# RENEWAA.net
KiCad netlist of a schematic drawn in Altium Designer
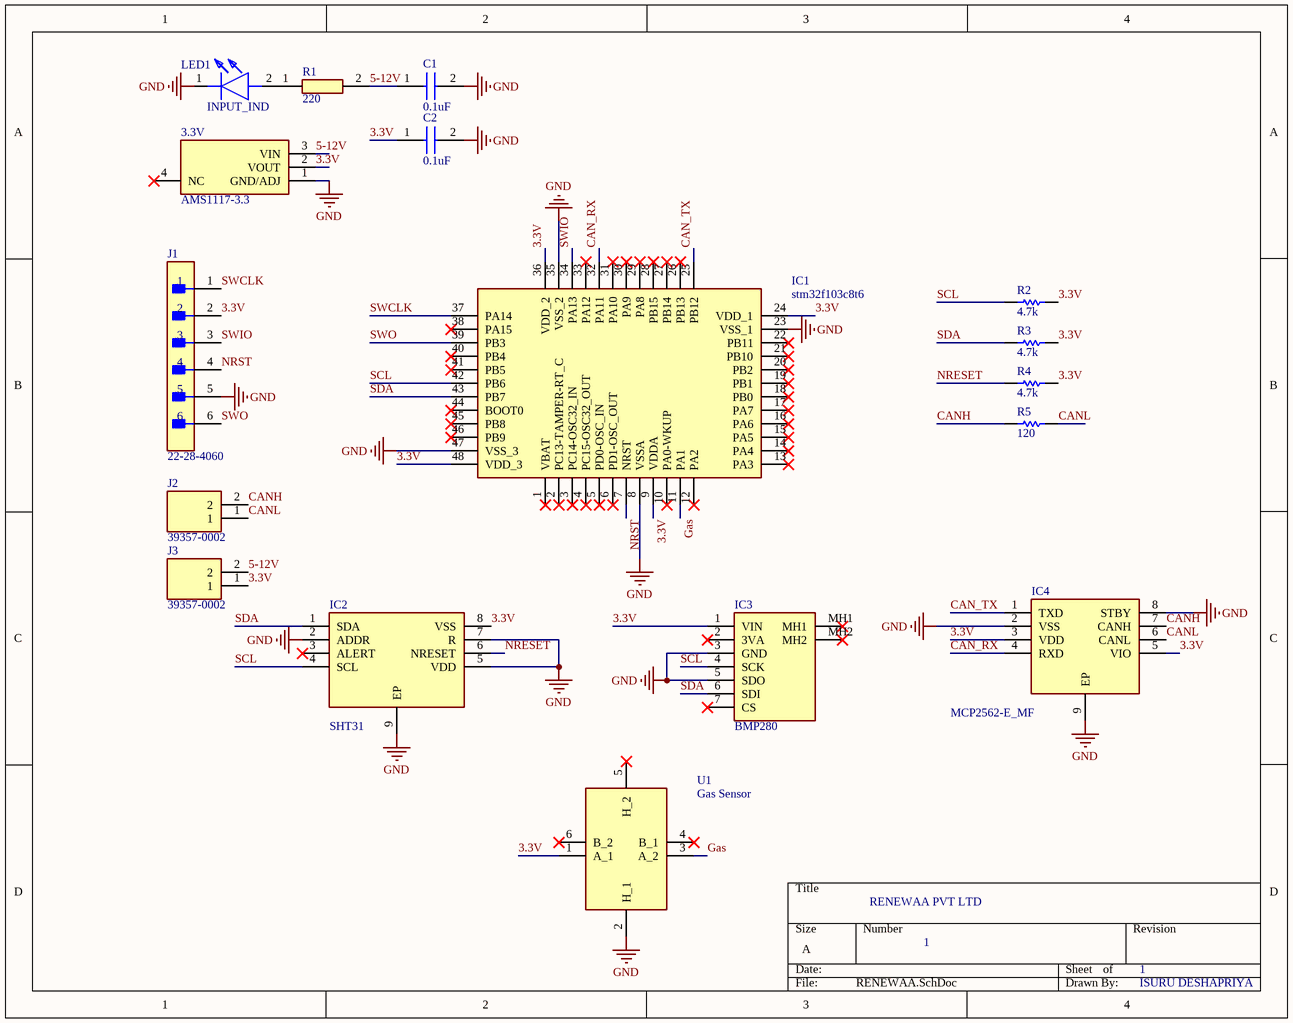
[diagram p0: RENEWAA.SchDoc]

(export (version "E")
  (design (tool "Eeschema 10.0.6"))
  (components
    (comp (ref "3.3V")
      (value "AMS1117-3.3")
      (footprint "SamacSys:SOT229P700X180-4N")
      (description "Integrated Circuit")
      (libsource (lib "*") (part "AMS1117-3.3"))
    )
    (comp (ref "C1")
      (value "0.1uF")
      (footprint "SamacSys:CAPC1005X56N")
      (description "Capacitor")
      (fields
        (field (name "MANUFACTURER_PART_NUMBER") "04024D106MAT2A")
        (field (name "MOUSER PART NUMBER") "581-04024D106MAT2A")
      )
      (libsource (lib "*") (part "04024D106MAT2A"))
    )
    (comp (ref "C2")
      (value "0.1uF")
      (footprint "SamacSys:CAPC1005X56N")
      (description "Capacitor")
      (fields
        (field (name "MANUFACTURER_PART_NUMBER") "04024D106MAT2A")
        (field (name "MOUSER PART NUMBER") "581-04024D106MAT2A")
      )
      (libsource (lib "*") (part "04024D106MAT2A"))
    )
    (comp (ref "IC1")
      (value "stm32f103c8t6")
      (footprint "SamacSys:QFP50P900X900X160-48N")
      (description "Integrated Circuit")
      (fields
        (field (name "MOUSER PART NUMBER") "511-STM32F103C8T6")
        (field (name "ARROW PART NUMBER") "STM32F103C8T6")
      )
      (libsource (lib "*") (part "stm32f103c8t6"))
    )
    (comp (ref "IC2")
      (value "SHT31")
      (footprint "SamacSys:SON50P250X250X100-9N-D")
      (description "Integrated Circuit")
      (fields
        (field (name "MANUFACTURER_PART_NUMBER") "SHT31-DIS-B10KS")
        (field (name "MOUSER PART NUMBER") "403-SHT31-DIS-B10KS")
      )
      (libsource (lib "*") (part "SHT31-DIS-B10KS"))
    )
    (comp (ref "IC3")
      (value "BMP280")
      (footprint "SamacSys:2651")
      (description "Integrated Circuit")
      (fields (field (name "MANUFACTURER_PART_NUMBER") "2651") (field (name "MOUSER PART NUMBER") "485-2651"))
      (libsource (lib "*") (part "2651"))
    )
    (comp (ref "IC4")
      (value "MCP2562-E_MF")
      (footprint "SamacSys:SON65P300X300X100-9N-D")
      (description "Integrated Circuit")
      (fields
        (field (name "MANUFACTURER_PART_NUMBER") "MCP2562-E/MF")
        (field (name "MOUSER PART NUMBER") "579-MCP2562-E/MF")
      )
      (libsource (lib "*") (part "MCP2562-E_MF"))
    )
    (comp (ref "J1")
      (value "22-28-4060")
      (footprint "FP-22-28-4060-MFG")
      (description "CONN HEADER VERT 6POS 2.54MM")
      (libsource (lib "Altium Content Vault") (part "f2cb566baf1c37ab5a3b8e90bbeafd6"))
    )
    (comp (ref "J2")
      (value "39357-0002")
      (footprint "SamacSys:393570002")
      (description "Connector")
      (fields (field (name "MOUSER PART NUMBER") "538-39357-0002"))
      (libsource (lib "*") (part "39357-0002"))
    )
    (comp (ref "J3")
      (value "39357-0002")
      (footprint "SamacSys:393570002")
      (description "Connector")
      (fields (field (name "MOUSER PART NUMBER") "538-39357-0002"))
      (libsource (lib "*") (part "39357-0002"))
    )
    (comp (ref "LED1")
      (value "INPUT_IND")
      (footprint "SamacSys:1221S2CFR2S2L2C")
      (description "LED")
      (fields (field (name "MANUFACTURER_PART_NUMBER") "12-21/S2C-FR2S2L/2C"))
      (libsource (lib "*") (part "12-21_S2C-FR2S2L_2C"))
    )
    (comp (ref "R1")
      (value "220")
      (footprint "SamacSys:RESC1005X40N")
      (description "Resistor")
      (fields
        (field (name "MANUFACTURER_PART_NUMBER") "CR0402-FX-2200GLF")
        (field (name "MOUSER PART NUMBER") "652-CR0402FX-2200GLF")
      )
      (libsource (lib "*") (part "CR0402-FX-2200GLF"))
    )
    (comp (ref "R2")
      (value "4.7k")
      (footprint "RESC3216X60X45ML15T20")
      (description "Chip Resistor, 4.7 KOhm, +/- 1%, 0.25 W, -55 to 155 degC, 1206 (3216 Metric), RoHS, Tape and Reel")
      (fields (field (name "MANUFACTURER") "Vishay Semiconductor") (field (name "TOLERANCE") "1%"))
      (libsource (lib "Altium Content Vault") (part "RES-2"))
    )
    (comp (ref "R3")
      (value "4.7k")
      (footprint "RESC3216X60X45ML15T20")
      (description "Chip Resistor, 4.7 KOhm, +/- 1%, 0.25 W, -55 to 155 degC, 1206 (3216 Metric), RoHS, Tape and Reel")
      (fields (field (name "MANUFACTURER") "Vishay Semiconductor") (field (name "TOLERANCE") "1%"))
      (libsource (lib "Altium Content Vault") (part "RES-2"))
    )
    (comp (ref "R4")
      (value "4.7k")
      (footprint "RESC3216X60X45ML15T20")
      (description "Chip Resistor, 4.7 KOhm, +/- 1%, 0.25 W, -55 to 155 degC, 1206 (3216 Metric), RoHS, Tape and Reel")
      (fields (field (name "MANUFACTURER") "Vishay Semiconductor") (field (name "TOLERANCE") "1%"))
      (libsource (lib "Altium Content Vault") (part "RES-2"))
    )
    (comp (ref "R5")
      (value "120")
      (footprint "RESC1609X55X30ML15T15")
      (description "Chip Resistor, 120 Ohm, +/- 1%, 0.1 W, -55 to 155 degC, 0603 (1608 Metric), RoHS, Tape and Reel")
      (fields (field (name "TOLERANCE") "1%") (field (name "MANUFACTURER") "Panasonic"))
      (libsource (lib "Altium Content Vault") (part "RES-2"))
    )
    (comp (ref "U1")
      (value "Gas Sensor")
      (footprint "SamacSys:60500009")
      (description "MQ-2")
      (fields
        (field (name "MANUFACTURER_PART_NUMBER") "605-00009")
        (field (name "MOUSER PART NUMBER") "619-605-00009")
      )
      (libsource (lib "*") (part "605-00009"))
    )
  )
  (nets
    (net (code "1") (name "/3.3V") (class "Default")
      (node (ref "3.3V") (pin "2") (pinfunction "VOUT_2") (pintype "passive"))
      (node (ref "C2") (pin "1") (pinfunction "1_1") (pintype "passive"))
      (node (ref "IC1") (pin "24") (pinfunction "VDD_1_24") (pintype "passive"))
      (node (ref "IC1") (pin "36") (pinfunction "VDD_2_36") (pintype "passive"))
      (node (ref "IC1") (pin "48") (pinfunction "VDD_3_48") (pintype "passive"))
      (node (ref "IC1") (pin "9") (pinfunction "VDDA_9") (pintype "passive"))
      (node (ref "IC2") (pin "8") (pinfunction "VSS_8") (pintype "passive"))
      (node (ref "IC3") (pin "1") (pinfunction "VIN_1") (pintype "passive"))
      (node (ref "IC4") (pin "3") (pinfunction "VDD_3") (pintype "power_in"))
      (node (ref "IC4") (pin "5") (pinfunction "VIO_5") (pintype "passive"))
      (node (ref "J1") (pin "2") (pinfunction "2_2") (pintype "passive"))
      (node (ref "J3") (pin "1") (pinfunction "1_1") (pintype "passive"))
      (node (ref "R2") (pin "2") (pinfunction "2_2") (pintype "passive"))
      (node (ref "R3") (pin "2") (pinfunction "2_2") (pintype "passive"))
      (node (ref "R4") (pin "2") (pinfunction "2_2") (pintype "passive"))
      (node (ref "U1") (pin "1") (pinfunction "A_1_1") (pintype "passive"))
    )
    (net (code "2") (name "/5-12V") (class "Default")
      (node (ref "3.3V") (pin "3") (pinfunction "VIN_3") (pintype "passive"))
      (node (ref "C1") (pin "1") (pinfunction "1_1") (pintype "passive"))
      (node (ref "J3") (pin "2") (pinfunction "2_2") (pintype "passive"))
      (node (ref "R1") (pin "2") (pinfunction "2_2") (pintype "passive"))
    )
    (net (code "3") (name "/CANH") (class "Default")
      (node (ref "IC4") (pin "7") (pinfunction "CANH_7") (pintype "passive"))
      (node (ref "J2") (pin "2") (pinfunction "2_2") (pintype "passive"))
      (node (ref "R5") (pin "1") (pinfunction "1_1") (pintype "passive"))
    )
    (net (code "4") (name "/CANL") (class "Default")
      (node (ref "IC4") (pin "6") (pinfunction "CANL_6") (pintype "passive"))
      (node (ref "J2") (pin "1") (pinfunction "1_1") (pintype "passive"))
      (node (ref "R5") (pin "2") (pinfunction "2_2") (pintype "passive"))
    )
    (net (code "5") (name "/CAN_RX") (class "Default")
      (node (ref "IC1") (pin "32") (pinfunction "PA11_32") (pintype "passive"))
      (node (ref "IC4") (pin "4") (pinfunction "RXD_4") (pintype "passive"))
    )
    (net (code "6") (name "/CAN_TX") (class "Default")
      (node (ref "IC1") (pin "25") (pinfunction "PB12_25") (pintype "passive"))
      (node (ref "IC4") (pin "1") (pinfunction "TXD_1") (pintype "passive"))
    )
    (net (code "7") (name "/Gas") (class "Default")
      (node (ref "IC1") (pin "11") (pinfunction "PA1_11") (pintype "passive"))
      (node (ref "U1") (pin "3") (pinfunction "A_2_3") (pintype "passive"))
    )
    (net (code "8") (name "/NRESET") (class "Default")
      (node (ref "IC2") (pin "6") (pinfunction "NRESET_6") (pintype "passive"))
      (node (ref "R4") (pin "1") (pinfunction "1_1") (pintype "passive"))
    )
    (net (code "9") (name "/NRST") (class "Default")
      (node (ref "IC1") (pin "7") (pinfunction "NRST_7") (pintype "passive"))
      (node (ref "J1") (pin "4") (pinfunction "4_4") (pintype "passive"))
    )
    (net (code "10") (name "/SCL") (class "Default")
      (node (ref "IC1") (pin "42") (pinfunction "PB6_42") (pintype "passive"))
      (node (ref "IC2") (pin "4") (pinfunction "SCL_4") (pintype "passive"))
      (node (ref "IC3") (pin "4") (pinfunction "SCK_4") (pintype "passive"))
      (node (ref "R2") (pin "1") (pinfunction "1_1") (pintype "passive"))
    )
    (net (code "11") (name "/SDA") (class "Default")
      (node (ref "IC1") (pin "43") (pinfunction "PB7_43") (pintype "passive"))
      (node (ref "IC2") (pin "1") (pinfunction "SDA_1") (pintype "passive"))
      (node (ref "IC3") (pin "6") (pinfunction "SDI_6") (pintype "passive"))
      (node (ref "R3") (pin "1") (pinfunction "1_1") (pintype "passive"))
    )
    (net (code "12") (name "/SWCLK") (class "Default")
      (node (ref "IC1") (pin "37") (pinfunction "PA14_37") (pintype "passive"))
      (node (ref "J1") (pin "1") (pinfunction "1_1") (pintype "passive"))
    )
    (net (code "13") (name "/SWIO") (class "Default")
      (node (ref "IC1") (pin "34") (pinfunction "PA13_34") (pintype "passive"))
      (node (ref "J1") (pin "3") (pinfunction "3_3") (pintype "passive"))
    )
    (net (code "14") (name "/SWO") (class "Default")
      (node (ref "IC1") (pin "39") (pinfunction "PB3_39") (pintype "passive"))
      (node (ref "J1") (pin "6") (pinfunction "6_6") (pintype "passive"))
    )
    (net (code "15") (name "GND") (class "Default")
      (node (ref "3.3V") (pin "1") (pinfunction "GND/ADJ_1") (pintype "passive"))
      (node (ref "C1") (pin "2") (pinfunction "2_2") (pintype "passive"))
      (node (ref "C2") (pin "2") (pinfunction "2_2") (pintype "passive"))
      (node (ref "IC1") (pin "23") (pinfunction "VSS_1_23") (pintype "passive"))
      (node (ref "IC1") (pin "35") (pinfunction "VSS_2_35") (pintype "passive"))
      (node (ref "IC1") (pin "47") (pinfunction "VSS_3_47") (pintype "passive"))
      (node (ref "IC1") (pin "8") (pinfunction "VSSA_8") (pintype "passive"))
      (node (ref "IC2") (pin "2") (pinfunction "ADDR_2") (pintype "passive"))
      (node (ref "IC2") (pin "5") (pinfunction "VDD_5") (pintype "passive"))
      (node (ref "IC2") (pin "7") (pinfunction "R_7") (pintype "passive"))
      (node (ref "IC2") (pin "9") (pinfunction "EP_9") (pintype "passive"))
      (node (ref "IC3") (pin "3") (pinfunction "GND_3") (pintype "passive"))
      (node (ref "IC3") (pin "5") (pinfunction "SDO_5") (pintype "passive"))
      (node (ref "IC4") (pin "2") (pinfunction "VSS_2") (pintype "power_in"))
      (node (ref "IC4") (pin "8") (pinfunction "STBY_8") (pintype "passive"))
      (node (ref "IC4") (pin "9") (pinfunction "EP_9") (pintype "passive"))
      (node (ref "J1") (pin "5") (pinfunction "5_5") (pintype "passive"))
      (node (ref "LED1") (pin "1") (pinfunction "K_1") (pintype "passive"))
      (node (ref "U1") (pin "2") (pinfunction "H_1_2") (pintype "passive"))
    )
    (net (code "16") (name "Net-(LED1-A)") (class "Default")
      (node (ref "LED1") (pin "2") (pinfunction "A_2") (pintype "passive"))
      (node (ref "R1") (pin "1") (pinfunction "1_1") (pintype "passive"))
    )
    (net (code "17") (name "unconnected-(3.3V-NC-Pad4)") (class "Default")
      (node (ref "3.3V") (pin "4") (pinfunction "NC_4") (pintype "passive+no_connect"))
    )
    (net (code "18") (name "unconnected-(IC1-BOOT0-Pad44)") (class "Default")
      (node (ref "IC1") (pin "44") (pinfunction "BOOT0_44") (pintype "passive+no_connect"))
    )
    (net (code "19") (name "unconnected-(IC1-PA0-WKUP-Pad10)") (class "Default")
      (node (ref "IC1") (pin "10") (pinfunction "PA0-WKUP_10") (pintype "passive+no_connect"))
    )
    (net (code "20") (name "unconnected-(IC1-PA2-Pad12)") (class "Default")
      (node (ref "IC1") (pin "12") (pinfunction "PA2_12") (pintype "passive+no_connect"))
    )
    (net (code "21") (name "unconnected-(IC1-PA3-Pad13)") (class "Default")
      (node (ref "IC1") (pin "13") (pinfunction "PA3_13") (pintype "passive+no_connect"))
    )
    (net (code "22") (name "unconnected-(IC1-PA4-Pad14)") (class "Default")
      (node (ref "IC1") (pin "14") (pinfunction "PA4_14") (pintype "passive+no_connect"))
    )
    (net (code "23") (name "unconnected-(IC1-PA5-Pad15)") (class "Default")
      (node (ref "IC1") (pin "15") (pinfunction "PA5_15") (pintype "passive+no_connect"))
    )
    (net (code "24") (name "unconnected-(IC1-PA6-Pad16)") (class "Default")
      (node (ref "IC1") (pin "16") (pinfunction "PA6_16") (pintype "passive+no_connect"))
    )
    (net (code "25") (name "unconnected-(IC1-PA7-Pad17)") (class "Default")
      (node (ref "IC1") (pin "17") (pinfunction "PA7_17") (pintype "passive+no_connect"))
    )
    (net (code "26") (name "unconnected-(IC1-PA8-Pad29)") (class "Default")
      (node (ref "IC1") (pin "29") (pinfunction "PA8_29") (pintype "passive+no_connect"))
    )
    (net (code "27") (name "unconnected-(IC1-PA9-Pad30)") (class "Default")
      (node (ref "IC1") (pin "30") (pinfunction "PA9_30") (pintype "passive+no_connect"))
    )
    (net (code "28") (name "unconnected-(IC1-PA10-Pad31)") (class "Default")
      (node (ref "IC1") (pin "31") (pinfunction "PA10_31") (pintype "passive+no_connect"))
    )
    (net (code "29") (name "unconnected-(IC1-PA12-Pad33)") (class "Default")
      (node (ref "IC1") (pin "33") (pinfunction "PA12_33") (pintype "passive+no_connect"))
    )
    (net (code "30") (name "unconnected-(IC1-PA15-Pad38)") (class "Default")
      (node (ref "IC1") (pin "38") (pinfunction "PA15_38") (pintype "passive+no_connect"))
    )
    (net (code "31") (name "unconnected-(IC1-PB0-Pad18)") (class "Default")
      (node (ref "IC1") (pin "18") (pinfunction "PB0_18") (pintype "passive+no_connect"))
    )
    (net (code "32") (name "unconnected-(IC1-PB1-Pad19)") (class "Default")
      (node (ref "IC1") (pin "19") (pinfunction "PB1_19") (pintype "passive+no_connect"))
    )
    (net (code "33") (name "unconnected-(IC1-PB2-Pad20)") (class "Default")
      (node (ref "IC1") (pin "20") (pinfunction "PB2_20") (pintype "passive+no_connect"))
    )
    (net (code "34") (name "unconnected-(IC1-PB4-Pad40)") (class "Default")
      (node (ref "IC1") (pin "40") (pinfunction "PB4_40") (pintype "passive+no_connect"))
    )
    (net (code "35") (name "unconnected-(IC1-PB5-Pad41)") (class "Default")
      (node (ref "IC1") (pin "41") (pinfunction "PB5_41") (pintype "passive+no_connect"))
    )
    (net (code "36") (name "unconnected-(IC1-PB8-Pad45)") (class "Default")
      (node (ref "IC1") (pin "45") (pinfunction "PB8_45") (pintype "passive+no_connect"))
    )
    (net (code "37") (name "unconnected-(IC1-PB9-Pad46)") (class "Default")
      (node (ref "IC1") (pin "46") (pinfunction "PB9_46") (pintype "passive+no_connect"))
    )
    (net (code "38") (name "unconnected-(IC1-PB10-Pad21)") (class "Default")
      (node (ref "IC1") (pin "21") (pinfunction "PB10_21") (pintype "passive+no_connect"))
    )
    (net (code "39") (name "unconnected-(IC1-PB11-Pad22)") (class "Default")
      (node (ref "IC1") (pin "22") (pinfunction "PB11_22") (pintype "passive+no_connect"))
    )
    (net (code "40") (name "unconnected-(IC1-PB13-Pad26)") (class "Default")
      (node (ref "IC1") (pin "26") (pinfunction "PB13_26") (pintype "passive+no_connect"))
    )
    (net (code "41") (name "unconnected-(IC1-PB14-Pad27)") (class "Default")
      (node (ref "IC1") (pin "27") (pinfunction "PB14_27") (pintype "passive+no_connect"))
    )
    (net (code "42") (name "unconnected-(IC1-PB15-Pad28)") (class "Default")
      (node (ref "IC1") (pin "28") (pinfunction "PB15_28") (pintype "passive+no_connect"))
    )
    (net (code "43") (name "unconnected-(IC1-PC13-TAMPER-RT_C-Pad2)") (class "Default")
      (node (ref "IC1") (pin "2") (pinfunction "PC13-TAMPER-RT_C_2") (pintype "passive+no_connect"))
    )
    (net (code "44") (name "unconnected-(IC1-PC14-OSC32_IN-Pad3)") (class "Default")
      (node (ref "IC1") (pin "3") (pinfunction "PC14-OSC32_IN_3") (pintype "passive+no_connect"))
    )
    (net (code "45") (name "unconnected-(IC1-PC15-OSC32_OUT-Pad4)") (class "Default")
      (node (ref "IC1") (pin "4") (pinfunction "PC15-OSC32_OUT_4") (pintype "passive+no_connect"))
    )
    (net (code "46") (name "unconnected-(IC1-PD0-OSC_IN-Pad5)") (class "Default")
      (node (ref "IC1") (pin "5") (pinfunction "PD0-OSC_IN_5") (pintype "passive+no_connect"))
    )
    (net (code "47") (name "unconnected-(IC1-PD1-OSC_OUT-Pad6)") (class "Default")
      (node (ref "IC1") (pin "6") (pinfunction "PD1-OSC_OUT_6") (pintype "passive+no_connect"))
    )
    (net (code "48") (name "unconnected-(IC1-VBAT-Pad1)") (class "Default")
      (node (ref "IC1") (pin "1") (pinfunction "VBAT_1") (pintype "passive+no_connect"))
    )
    (net (code "49") (name "unconnected-(IC2-ALERT-Pad3)") (class "Default")
      (node (ref "IC2") (pin "3") (pinfunction "ALERT_3") (pintype "passive+no_connect"))
    )
    (net (code "50") (name "unconnected-(IC3-3VA-Pad2)") (class "Default")
      (node (ref "IC3") (pin "2") (pinfunction "3VA_2") (pintype "passive+no_connect"))
    )
    (net (code "51") (name "unconnected-(IC3-CS-Pad7)") (class "Default")
      (node (ref "IC3") (pin "7") (pinfunction "CS_7") (pintype "passive+no_connect"))
    )
    (net (code "52") (name "unconnected-(IC3-PadMH1)") (class "Default")
      (node (ref "IC3") (pin "MH1") (pinfunction "MH1_MH1") (pintype "passive+no_connect"))
    )
    (net (code "53") (name "unconnected-(IC3-PadMH2)") (class "Default")
      (node (ref "IC3") (pin "MH2") (pinfunction "MH2_MH2") (pintype "passive+no_connect"))
    )
    (net (code "54") (name "unconnected-(U1-B_1-Pad4)") (class "Default")
      (node (ref "U1") (pin "4") (pinfunction "B_1_4") (pintype "passive+no_connect"))
    )
    (net (code "55") (name "unconnected-(U1-B_2-Pad6)") (class "Default")
      (node (ref "U1") (pin "6") (pinfunction "B_2_6") (pintype "passive+no_connect"))
    )
    (net (code "56") (name "unconnected-(U1-H_2-Pad5)") (class "Default")
      (node (ref "U1") (pin "5") (pinfunction "H_2_5") (pintype "passive+no_connect"))
    )
  )
)
